# Adapter-IO4-Breakout.net
KiCad netlist of a schematic drawn in EAGLE
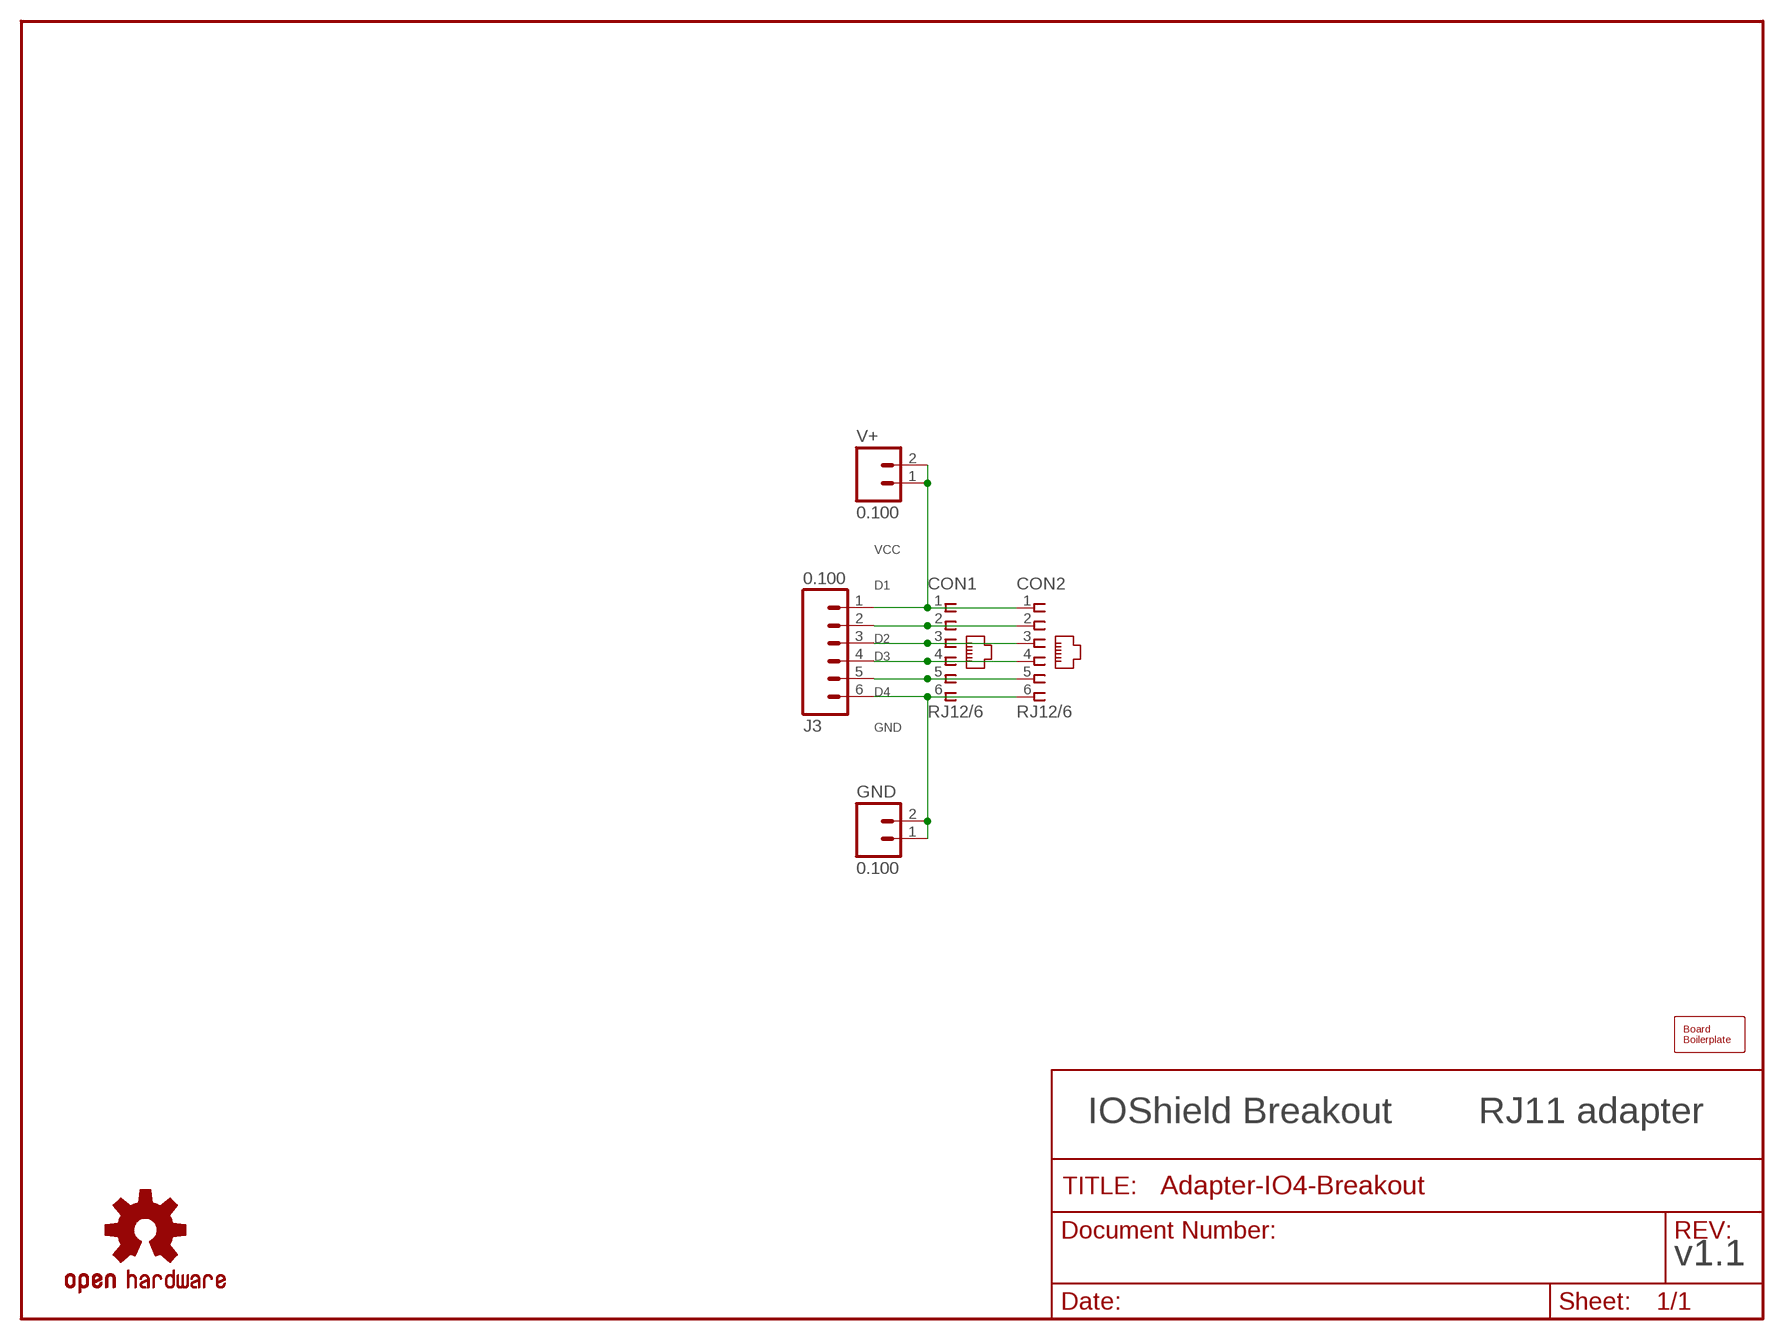
[diagram p0: schematic, sheet 1]

(export (version "E")
  (design (tool "Eeschema 10.0.6"))
  (components
    (comp (ref "BOARD1")
      (value "BOARD")
      (footprint "eagle-import:BOARD-SEEED5X5-NOHOLES")
      (libsource (lib "eagle-import") (part "BOARD50X50-NOHOLES"))
    )
    (comp (ref "CON1")
      (value "RJ12/6")
      (footprint "eagle-import:RJ25-PANEL")
      (libsource (lib "eagle-import") (part "CONNECTOR-RJ25-6P6C"))
    )
    (comp (ref "CON2")
      (value "RJ12/6")
      (footprint "eagle-import:RJ25-PANEL")
      (libsource (lib "eagle-import") (part "CONNECTOR-RJ25-6P6C"))
    )
    (comp (ref "GND")
      (value "0.100")
      (footprint "eagle-import:1X02_LOCK")
      (libsource (lib "eagle-import") (part "CONNECTOR-M021X02-LOCK"))
    )
    (comp (ref "J3")
      (value "0.100")
      (footprint "eagle-import:1X06_LOCK")
      (libsource (lib "eagle-import") (part "CONNECTOR-M06LOCK"))
    )
    (comp (ref "U$1")
      (value "OSHW")
      (footprint "eagle-import:OSHW-LOGO-M")
      (libsource (lib "eagle-import") (part "OSHW-LOGOM"))
    )
    (comp (ref "V+")
      (value "0.100")
      (footprint "eagle-import:1X02_LOCK")
      (libsource (lib "eagle-import") (part "CONNECTOR-M021X02-LOCK"))
    )
  )
  (nets
    (net (code "1") (name "/D1") (class "Default")
      (node (ref "CON1") (pin "2") (pinfunction "2_2") (pintype "passive"))
      (node (ref "CON2") (pin "2") (pinfunction "2_2") (pintype "passive"))
      (node (ref "J3") (pin "2") (pinfunction "2_2") (pintype "passive"))
    )
    (net (code "2") (name "/D2") (class "Default")
      (node (ref "CON1") (pin "3") (pinfunction "3_3") (pintype "passive"))
      (node (ref "CON2") (pin "3") (pinfunction "3_3") (pintype "passive"))
      (node (ref "J3") (pin "3") (pinfunction "3_3") (pintype "passive"))
    )
    (net (code "3") (name "/D3") (class "Default")
      (node (ref "CON1") (pin "4") (pinfunction "4_4") (pintype "passive"))
      (node (ref "CON2") (pin "4") (pinfunction "4_4") (pintype "passive"))
      (node (ref "J3") (pin "4") (pinfunction "4_4") (pintype "passive"))
    )
    (net (code "4") (name "/D4") (class "Default")
      (node (ref "CON1") (pin "5") (pinfunction "5_5") (pintype "passive"))
      (node (ref "CON2") (pin "5") (pinfunction "5_5") (pintype "passive"))
      (node (ref "J3") (pin "5") (pinfunction "5_5") (pintype "passive"))
    )
    (net (code "5") (name "/GND") (class "Default")
      (node (ref "CON1") (pin "6") (pinfunction "6_6") (pintype "passive"))
      (node (ref "CON2") (pin "6") (pinfunction "6_6") (pintype "passive"))
      (node (ref "GND") (pin "1") (pinfunction "A_1") (pintype "passive"))
      (node (ref "GND") (pin "2") (pinfunction "B_2") (pintype "passive"))
      (node (ref "J3") (pin "6") (pinfunction "6_6") (pintype "passive"))
    )
    (net (code "6") (name "/VCC") (class "Default")
      (node (ref "CON1") (pin "1") (pinfunction "1_1") (pintype "passive"))
      (node (ref "CON2") (pin "1") (pinfunction "1_1") (pintype "passive"))
      (node (ref "J3") (pin "1") (pinfunction "1_1") (pintype "passive"))
      (node (ref "V+") (pin "1") (pinfunction "A_1") (pintype "passive"))
      (node (ref "V+") (pin "2") (pinfunction "B_2") (pintype "passive"))
    )
  )
)
